# Sensor_Board.net
KiCad netlist of a schematic drawn in Altium Designer
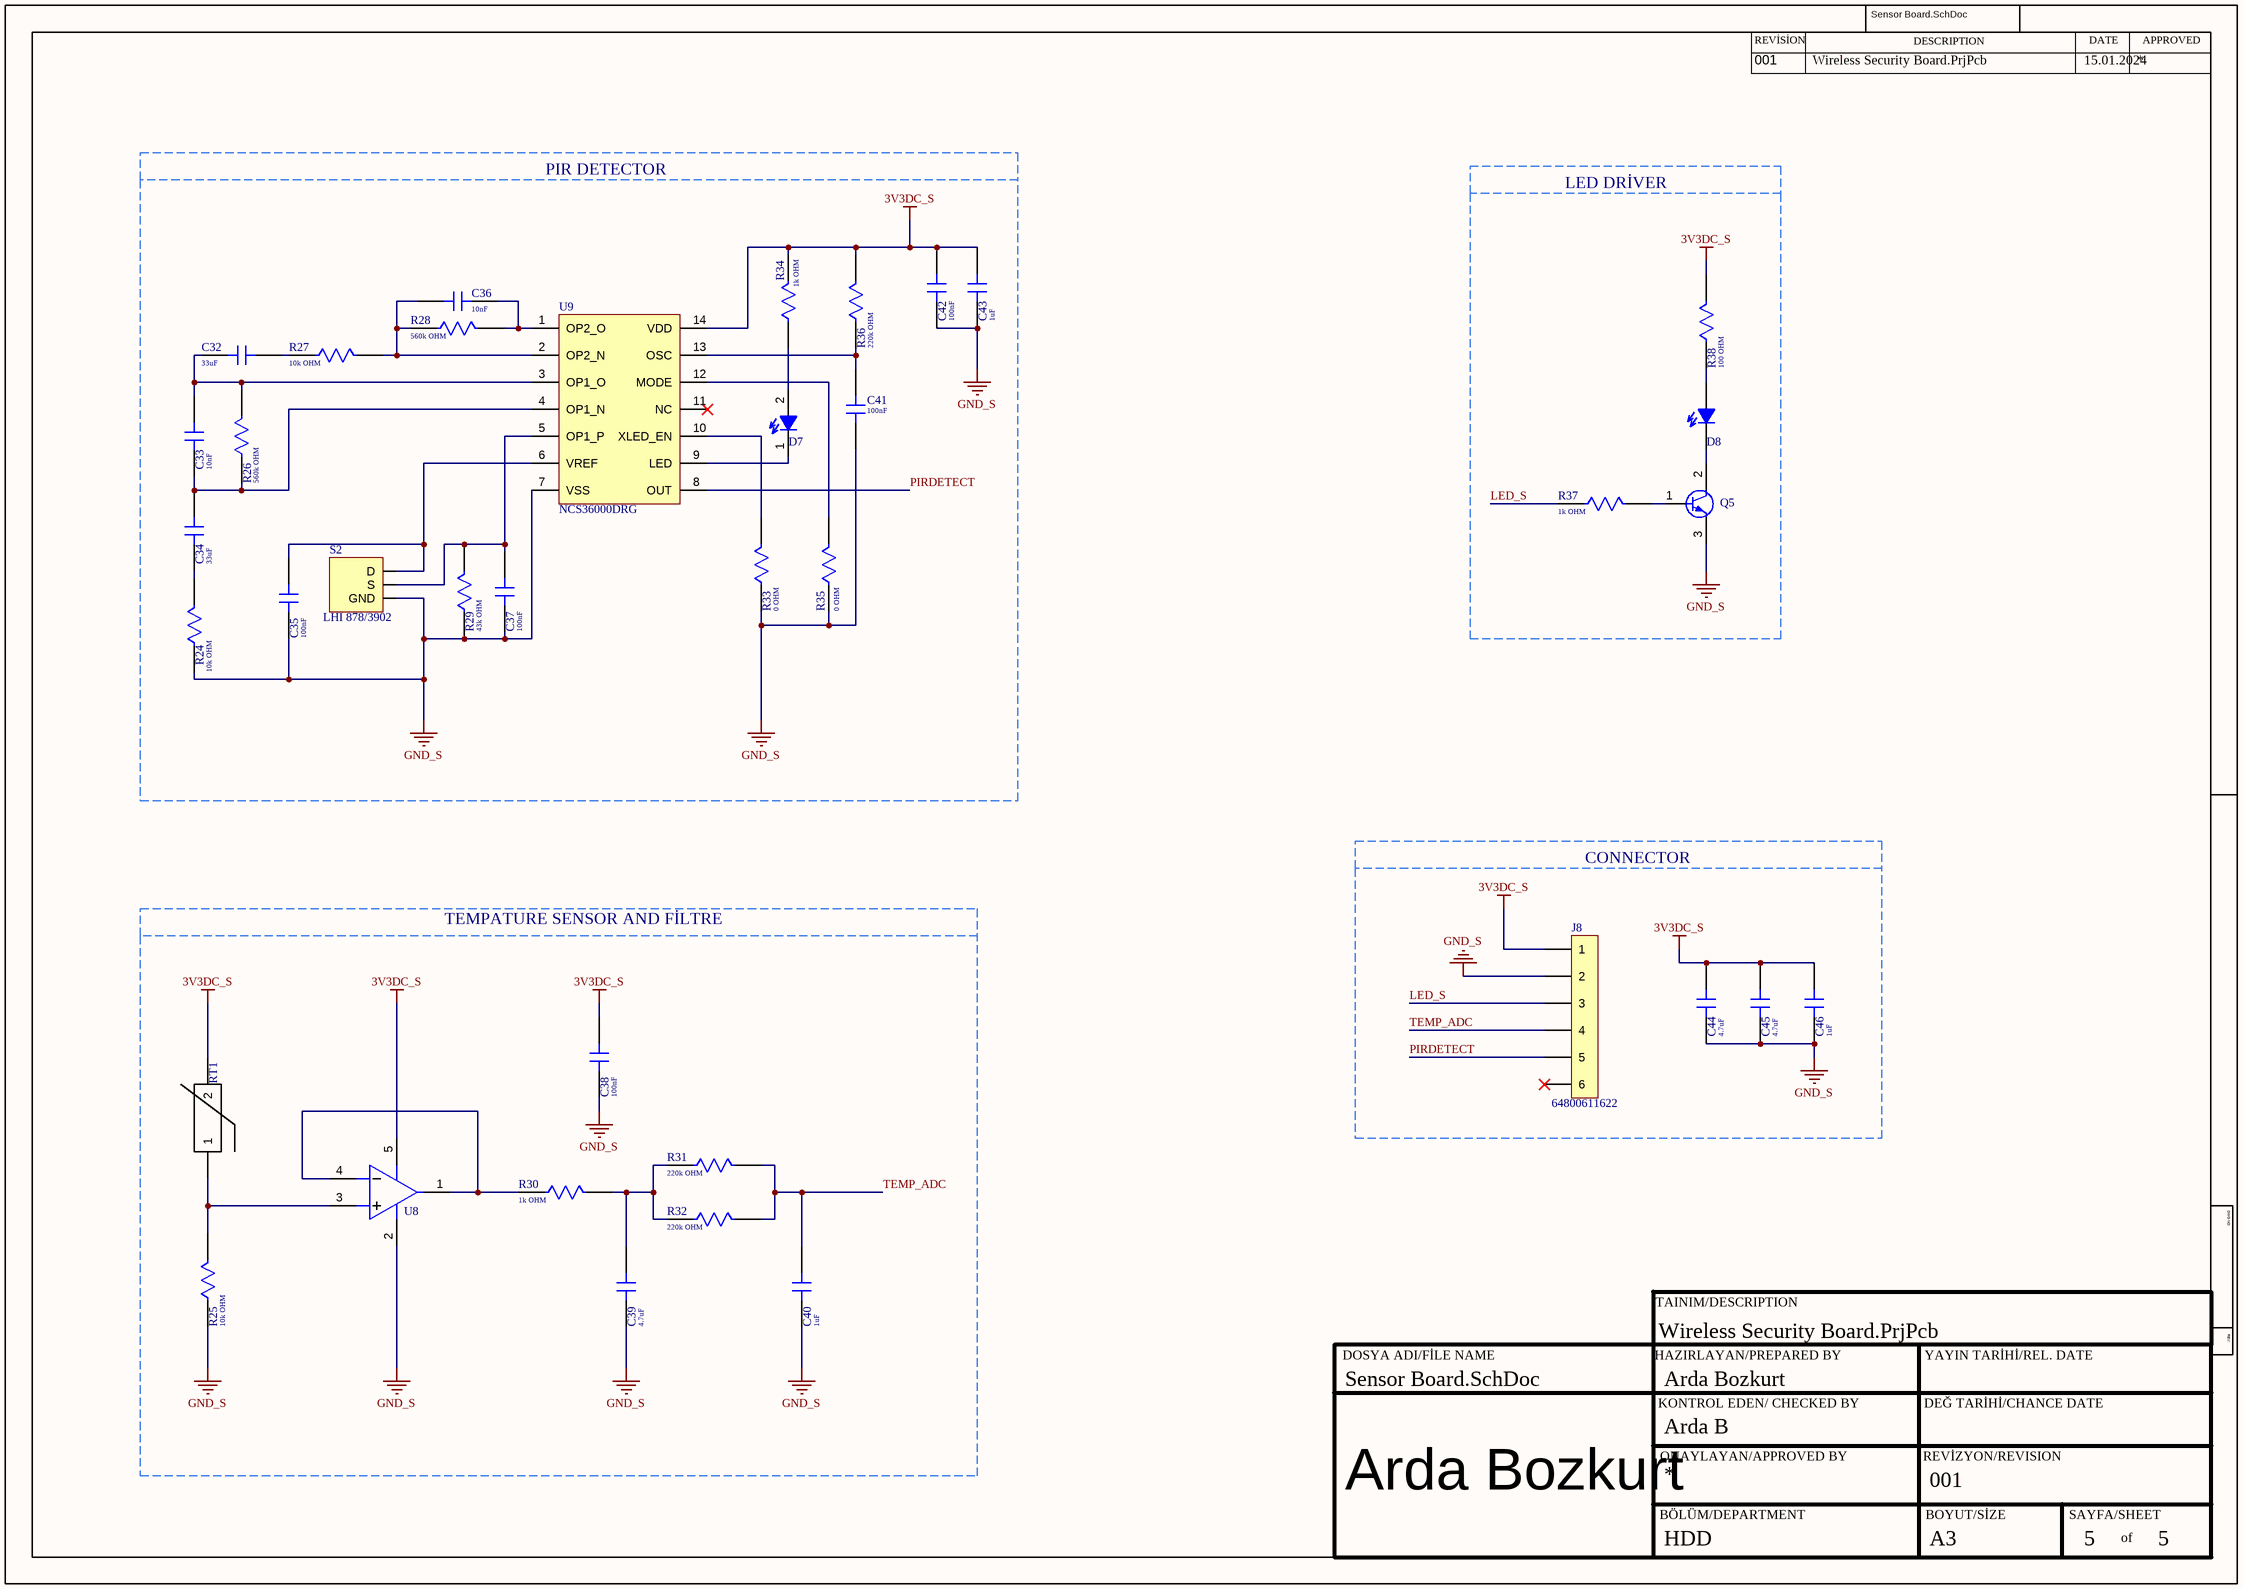
[diagram p0: Sensor Board.SchDoc]

(export (version "E")
  (design (tool "Eeschema 10.0.6"))
  (components
    (comp (ref "C32")
      (value "33uF")
      (footprint "CAP 1206")
      (description "C Series 1206 33 uF 16 V ±20 % Tolerance X5R SMT Multilayer Ceramic Capacitor")
      (fields
        (field (name "MANUFACTURER") "TDK")
        (field (name "MANUFACTURER PART NUMBER") "C3216X5R1C336M160AB")
        (field (name "DESIGNED BY.") "Arda B.")
      )
      (libsource (lib "FİRST.PROJECT.LİBRARY.~(1)") (part "CAP CER 33uF 1206"))
    )
    (comp (ref "C33")
      (value "10nF")
      (footprint "CAP-0603")
      (description "0603 16V X7R .01uF 10% multilayer ceramic capacitor")
      (fields
        (field (name "MANUFACTURER") "Walsin Technologies")
        (field (name "MANUFACTURER PART NUMBER") "0603B103K160CT")
        (field (name "DESIGNED BY") "Arda B.")
      )
      (libsource (lib "FİRST.PROJECT.LİBRARY.~(1)") (part "CAP CER 10nF 0603"))
    )
    (comp (ref "C34")
      (value "33uF")
      (footprint "CAP 1206")
      (description "C Series 1206 33 uF 16 V ±20 % Tolerance X5R SMT Multilayer Ceramic Capacitor")
      (fields
        (field (name "MANUFACTURER") "TDK")
        (field (name "MANUFACTURER PART NUMBER") "C3216X5R1C336M160AB")
        (field (name "DESIGNED BY.") "Arda B.")
      )
      (libsource (lib "FİRST.PROJECT.LİBRARY.~(1)") (part "CAP CER 33uF 1206"))
    )
    (comp (ref "C35")
      (value "100nF")
      (footprint "CAP-0805")
      (description "Multilayer Ceramic Capacitor, 0.1 uF, 50 V, ± 10%, X7R, 0805 [2012 Metric]")
      (fields
        (field (name "MANUFACTURER") "Kyocera AVX")
        (field (name "MANUFACTURER PART NUMBER") "08055C104KAT2A")
        (field (name "DESIGNED BY") "Arda B.")
      )
      (libsource (lib "FİRST.PROJECT.LİBRARY.~(1)") (part "CAP CER 100nF 0805"))
    )
    (comp (ref "C36")
      (value "10nF")
      (footprint "CAP-0603")
      (description "0603 16V X7R .01uF 10% multilayer ceramic capacitor")
      (fields
        (field (name "MANUFACTURER") "Walsin Technologies")
        (field (name "MANUFACTURER PART NUMBER") "0603B103K160CT")
        (field (name "DESIGNED BY") "Arda B.")
      )
      (libsource (lib "FİRST.PROJECT.LİBRARY.~(1)") (part "CAP CER 10nF 0603"))
    )
    (comp (ref "C37")
      (value "100nF")
      (footprint "CAP-0805")
      (description "Multilayer Ceramic Capacitor, 0.1 uF, 50 V, ± 10%, X7R, 0805 [2012 Metric]")
      (fields
        (field (name "MANUFACTURER") "Kyocera AVX")
        (field (name "MANUFACTURER PART NUMBER") "08055C104KAT2A")
        (field (name "DESIGNED BY") "Arda B.")
      )
      (libsource (lib "FİRST.PROJECT.LİBRARY.~(1)") (part "CAP CER 100nF 0805"))
    )
    (comp (ref "C38")
      (value "100nF")
      (footprint "CAP-0603")
      (description "Capacitor, 0.1UF, 100V, MLCC, 0603;")
      (fields
        (field (name "MANUFACTURER") "KEMET")
        (field (name "MANUFACTURER PART NUMBER") "C0603C104K1RACTU")
        (field (name "DESIGNED BY") "Arda B.")
      )
      (libsource (lib "FİRST.PROJECT.LİBRARY.~(1)") (part "CAP CER 100nF 0603"))
    )
    (comp (ref "C39")
      (value "4.7uF")
      (footprint "CAP-0805")
      (description "Multilayer Ceramic Capacitor, 4.7 uF, 25 V, ± 10%, X5R, 0805 [2012 Metric]")
      (fields
        (field (name "MANUFACTURER") "Samsung")
        (field (name "MANUFACTURER PART NUMBER") "CL21A475KAQNNNE")
        (field (name "DESIGNED BY") "Arda B.")
      )
      (libsource (lib "FİRST.PROJECT.LİBRARY.~(1)") (part "CAP CER 4.7uF 0805"))
    )
    (comp (ref "C40")
      (value "1uF")
      (footprint "CAP-0805")
      (description "Multilayer Ceramic Capacitor, 1 uF, 25 V, ± 10%, X7R, 0805 [2012 Metric]")
      (fields
        (field (name "MANUFACTURER") "Samsung")
        (field (name "MANUFACTURER PART NUMBER") "CL21B105KAFNNNE")
        (field (name "DESIGNED BY") "Arda B.")
      )
      (libsource (lib "FİRST.PROJECT.LİBRARY.~(1)") (part "CAP CER 1uF 0805"))
    )
    (comp (ref "C41")
      (value "100nF")
      (footprint "CAP-0805")
      (description "Multilayer Ceramic Capacitor, 0.1 uF, 50 V, ± 10%, X7R, 0805 [2012 Metric]")
      (fields
        (field (name "MANUFACTURER") "Kyocera AVX")
        (field (name "MANUFACTURER PART NUMBER") "08055C104KAT2A")
        (field (name "DESIGNED BY") "Arda B.")
      )
      (libsource (lib "FİRST.PROJECT.LİBRARY.~(1)") (part "CAP CER 100nF 0805"))
    )
    (comp (ref "C42")
      (value "100nF")
      (footprint "CAP-0805")
      (description "Multilayer Ceramic Capacitor, 0.1 uF, 50 V, ± 10%, X7R, 0805 [2012 Metric]")
      (fields
        (field (name "MANUFACTURER") "Kyocera AVX")
        (field (name "MANUFACTURER PART NUMBER") "08055C104KAT2A")
        (field (name "DESIGNED BY") "Arda B.")
      )
      (libsource (lib "FİRST.PROJECT.LİBRARY.~(1)") (part "CAP CER 100nF 0805"))
    )
    (comp (ref "C43")
      (value "1uF")
      (footprint "CAP-0805")
      (description "Multilayer Ceramic Capacitor, 1 uF, 25 V, ± 10%, X7R, 0805 [2012 Metric]")
      (fields
        (field (name "MANUFACTURER") "Samsung")
        (field (name "MANUFACTURER PART NUMBER") "CL21B105KAFNNNE")
        (field (name "DESIGNED BY") "Arda B.")
      )
      (libsource (lib "FİRST.PROJECT.LİBRARY.~(1)") (part "CAP CER 1uF 0805"))
    )
    (comp (ref "C44")
      (value "4.7uF")
      (footprint "CAP-0805")
      (description "Multilayer Ceramic Capacitor, 4.7 uF, 25 V, ± 10%, X5R, 0805 [2012 Metric]")
      (fields
        (field (name "MANUFACTURER") "Samsung")
        (field (name "MANUFACTURER PART NUMBER") "CL21A475KAQNNNE")
        (field (name "DESIGNED BY") "Arda B.")
      )
      (libsource (lib "FİRST.PROJECT.LİBRARY.~(1)") (part "CAP CER 4.7uF 0805"))
    )
    (comp (ref "C45")
      (value "4.7uF")
      (footprint "CAP-0805")
      (description "Multilayer Ceramic Capacitor, 4.7 uF, 25 V, ± 10%, X5R, 0805 [2012 Metric]")
      (fields
        (field (name "MANUFACTURER") "Samsung")
        (field (name "MANUFACTURER PART NUMBER") "CL21A475KAQNNNE")
        (field (name "DESIGNED BY") "Arda B.")
      )
      (libsource (lib "FİRST.PROJECT.LİBRARY.~(1)") (part "CAP CER 4.7uF 0805"))
    )
    (comp (ref "C46")
      (value "1uF")
      (footprint "CAP-0805")
      (description "Multilayer Ceramic Capacitor, 1 uF, 25 V, ± 10%, X7R, 0805 [2012 Metric]")
      (fields
        (field (name "MANUFACTURER") "Samsung")
        (field (name "MANUFACTURER PART NUMBER") "CL21B105KAFNNNE")
        (field (name "DESIGNED BY") "Arda B.")
      )
      (libsource (lib "FİRST.PROJECT.LİBRARY.~(1)") (part "CAP CER 1uF 0805"))
    )
    (comp (ref "D7")
      (value "LTST-C171GKT")
      (footprint "LED GREEN 0805")
      (description "LED Low-Power Uni-Color Green 565nm 2.1V 2-Pin Chip LED T/R")
      (fields (field (name "MANUFACTURER") "Vishay Lite-On") (field (name "DESIGNED BY") "Arda B."))
      (libsource (lib "FİRST.PROJECT.LİBRARY.~(1)") (part "LED GREEN 0805"))
    )
    (comp (ref "D8")
      (value "LS R976-NR-1")
      (footprint "LED RED 0805")
      (description "LED Uni-Color Super Red 645nm 2-Pin Chip 0805(2012Metric) T/R")
      (fields
        (field (name "MANUFACTURER") "Osram Opto")
        (field (name "MANUFACTURER PART NUMBER") "LSR976-NR-1")
        (field (name "DESIGNED BY") "Arda B.")
      )
      (libsource (lib "FİRST.PROJECT.LİBRARY.~(1)") (part "LED RED 0805"))
    )
    (comp (ref "J8")
      (value "64800611622")
      (footprint "PİN_HEADER_1X6")
      (description "WR-WTB Wire-to-Board Connectors 1.50 mm")
      (fields (field (name "MANUFACTURER") "Wurth Electronics") (field (name "DESIGNED BY.") "Arda B."))
      (libsource (lib "FİRST.PROJECT.LİBRARY.~(1)") (part "PİN HEADER 1X6"))
    )
    (comp (ref "Q5")
      (value "MMBT3904-7-F")
      (footprint "SOT23-3")
      (description "Transistor General Purpose BJT NPN 40 Volt 0.2A Automotive 3-Pin SOT-23")
      (fields (field (name "MANUFACTURER") "Diodes Zetex") (field (name "DESIGNED BY") "Arda B."))
      (libsource (lib "FİRST.PROJECT.LİBRARY.~(1)") (part "MMBT3904-7-F"))
    )
    (comp (ref "R24")
      (value "10k OHM")
      (footprint "RES-0603")
      (description "SMD Chip Resistor, 10 kOhm, ± 1%, 100 mW, 0603 [1608 Metric], Thick Film, General Purpose")
      (fields
        (field (name "MANUFACTURER") "Yageo")
        (field (name "MANUFACTURER PART NUMBER") "RC0603FR-0710KL")
        (field (name "DESIGNED BY") "Arda B.")
      )
      (libsource (lib "FİRST.PROJECT.LİBRARY.~(1)") (part "RES 10K OHM 0603"))
    )
    (comp (ref "R25")
      (value "10k OHM")
      (footprint "RES-0603")
      (description "SMD Chip Resistor, 10 kOhm, ± 1%, 100 mW, 0603 [1608 Metric], Thick Film, General Purpose")
      (fields
        (field (name "MANUFACTURER") "Yageo")
        (field (name "MANUFACTURER PART NUMBER") "RC0603FR-0710KL")
        (field (name "DESIGNED BY") "Arda B.")
      )
      (libsource (lib "FİRST.PROJECT.LİBRARY.~(1)") (part "RES 10K OHM 0603"))
    )
    (comp (ref "R26")
      (value "560k OHM")
      (footprint "RES-0603")
      (description "Res Thick Film 0603 560K Ohm 1% 1/10W ±100ppm/°C Molded SMD SMD Paper T/R")
      (fields
        (field (name "MANUFACTURER") "Stackpole Electronics")
        (field (name "MANUFACTURER PART NUMBER") "RMCF0603FT560K")
        (field (name "DESIGNED BY") "Arda B.")
      )
      (libsource (lib "FİRST.PROJECT.LİBRARY.~(1)") (part "RES 560K OHM 0603"))
    )
    (comp (ref "R27")
      (value "10k OHM")
      (footprint "RES-0603")
      (description "SMD Chip Resistor, 10 kOhm, ± 1%, 100 mW, 0603 [1608 Metric], Thick Film, General Purpose")
      (fields
        (field (name "MANUFACTURER") "Yageo")
        (field (name "MANUFACTURER PART NUMBER") "RC0603FR-0710KL")
        (field (name "DESIGNED BY") "Arda B.")
      )
      (libsource (lib "FİRST.PROJECT.LİBRARY.~(1)") (part "RES 10K OHM 0603"))
    )
    (comp (ref "R28")
      (value "560k OHM")
      (footprint "RES-0603")
      (description "Res Thick Film 0603 560K Ohm 1% 1/10W ±100ppm/°C Molded SMD SMD Paper T/R")
      (fields
        (field (name "MANUFACTURER") "Stackpole Electronics")
        (field (name "MANUFACTURER PART NUMBER") "RMCF0603FT560K")
        (field (name "DESIGNED BY") "Arda B.")
      )
      (libsource (lib "FİRST.PROJECT.LİBRARY.~(1)") (part "RES 560K OHM 0603"))
    )
    (comp (ref "R29")
      (value "43k OHM")
      (footprint "RES-0603")
      (description "Res Thick Film 0603 43K Ohm 1% 1/10W ±100ppm/°C Molded SMD SMD Paper T/R")
      (fields
        (field (name "MANUFACTURER") "Stackpole Electronics")
        (field (name "MANUFACTURER PART NUMBER") "RMCF0603FT43K0")
        (field (name "DESIGNED BY") "Arda B.")
      )
      (libsource (lib "FİRST.PROJECT.LİBRARY.~(1)") (part "RES 43K OHM 0603"))
    )
    (comp (ref "R30")
      (value "1k OHM")
      (footprint "RES-0603")
      (description "Res Thick Film 0603 1K Ohm 1% 0.1W(1/10W) ±100ppm/C Pad SMD Automotive T/R")
      (fields
        (field (name "MANUFACTURER") "Stackpole Electronics")
        (field (name "MANUFACTURER PART NUMBER") "RMCF0603FT1K00")
        (field (name "DESIGNED BY") "Arda B.")
      )
      (libsource (lib "FİRST.PROJECT.LİBRARY.~(1)") (part "RES 1K OHM 0603"))
    )
    (comp (ref "R31")
      (value "220k OHM")
      (footprint "RES-0603")
      (description "Res Thick Film 0603 220K Ohm 1% 0.1W(1/10W) ±100ppm/C Pad SMD T/R")
      (fields
        (field (name "MANUFACTURER") "Walsin Technologies")
        (field (name "MANUFACTURER PART NUMBER") "WR06X2203FTL")
        (field (name "DESIGNED BY") "Arda B.")
      )
      (libsource (lib "FİRST.PROJECT.LİBRARY.~(1)") (part "RES 220K OHM 0603"))
    )
    (comp (ref "R32")
      (value "220k OHM")
      (footprint "RES-0603")
      (description "Res Thick Film 0603 220K Ohm 1% 0.1W(1/10W) ±100ppm/C Pad SMD T/R")
      (fields
        (field (name "MANUFACTURER") "Walsin Technologies")
        (field (name "MANUFACTURER PART NUMBER") "WR06X2203FTL")
        (field (name "DESIGNED BY") "Arda B.")
      )
      (libsource (lib "FİRST.PROJECT.LİBRARY.~(1)") (part "RES 220K OHM 0603"))
    )
    (comp (ref "R33")
      (value "0 OHM")
      (footprint "RES-0603")
      (description "Res Thkflm 0603 0 Ohm Jumper 1/10W 100Ppm/ C Smd Rohs Compliant: Yes")
      (fields
        (field (name "MANUFACTURER") "Stackpole Electronics")
        (field (name "MANUFACTURER PART NUMBER") "RMCF0603ZT0R00")
        (field (name "DESIGNED BY") "Arda B.")
      )
      (libsource (lib "FİRST.PROJECT.LİBRARY.~(1)") (part "RES 0K OHM 0603"))
    )
    (comp (ref "R34")
      (value "1k OHM")
      (footprint "RES-0603")
      (description "Res Thick Film 0603 1K Ohm 1% 0.1W(1/10W) ±100ppm/C Pad SMD Automotive T/R")
      (fields
        (field (name "MANUFACTURER") "Stackpole Electronics")
        (field (name "MANUFACTURER PART NUMBER") "RMCF0603FT1K00")
        (field (name "DESIGNED BY") "Arda B.")
      )
      (libsource (lib "FİRST.PROJECT.LİBRARY.~(1)") (part "RES 1K OHM 0603"))
    )
    (comp (ref "R35")
      (value "0 OHM")
      (footprint "RES-0603")
      (description "Res Thkflm 0603 0 Ohm Jumper 1/10W 100Ppm/ C Smd Rohs Compliant: Yes")
      (fields
        (field (name "MANUFACTURER") "Stackpole Electronics")
        (field (name "MANUFACTURER PART NUMBER") "RMCF0603ZT0R00")
        (field (name "DESIGNED BY") "Arda B.")
      )
      (libsource (lib "FİRST.PROJECT.LİBRARY.~(1)") (part "RES 0K OHM 0603"))
    )
    (comp (ref "R36")
      (value "220k OHM")
      (footprint "RES-0603")
      (description "Res Thick Film 0603 220K Ohm 1% 0.1W(1/10W) ±100ppm/C Pad SMD T/R")
      (fields
        (field (name "MANUFACTURER") "Walsin Technologies")
        (field (name "MANUFACTURER PART NUMBER") "WR06X2203FTL")
        (field (name "DESIGNED BY") "Arda B.")
      )
      (libsource (lib "FİRST.PROJECT.LİBRARY.~(1)") (part "RES 220K OHM 0603"))
    )
    (comp (ref "R37")
      (value "1k OHM")
      (footprint "RES-0603")
      (description "Res Thick Film 0603 1K Ohm 1% 0.1W(1/10W) ±100ppm/C Pad SMD Automotive T/R")
      (fields
        (field (name "MANUFACTURER") "Stackpole Electronics")
        (field (name "MANUFACTURER PART NUMBER") "RMCF0603FT1K00")
        (field (name "DESIGNED BY") "Arda B.")
      )
      (libsource (lib "FİRST.PROJECT.LİBRARY.~(1)") (part "RES 1K OHM 0603"))
    )
    (comp (ref "R38")
      (value "100 OHM")
      (footprint "RES-0603")
      (description "Res Thick Film 0603 100 Ohm 1% 1/10W ±100ppm/°C Molded SMD SMD Paper T/R")
      (fields
        (field (name "MANUFACTURER") "Stackpole Electronics")
        (field (name "MANUFACTURER PART NUMBER") "RMCF0603FT100R")
        (field (name "DESIGNED BY") "Arda B.")
      )
      (libsource (lib "FİRST.PROJECT.LİBRARY.~(1)") (part "RES 100 OHM 0603"))
    )
    (comp (ref "RT1")
      (value "TFPT1206L1002FM")
      (footprint "TFPT1206")
      (description "Thermistor PTC 10K Ohm 1% 2-Pin 1206 Surface Mount Solder Pad T/R Automotive")
      (fields
        (field (name "MANUFACTURER") "Vishay Dale")
        (field (name "TOLERANCE") "1%")
        (field (name "DESIGNED BY") "Arda B.")
      )
      (libsource (lib "FİRST.PROJECT.LİBRARY.~(1)") (part "TFPT1206L1002FM"))
    )
    (comp (ref "S2")
      (value "LHI 878/3902")
      (footprint "TO-5-3")
      (description "SENSOR PYRO DETECTOR DUAL MOTION")
      (libsource (lib "FİRST.PROJECT.LİBRARY.~(1)") (part "LHI878/3902"))
    )
    (comp (ref "U8")
      (value "OPA314AIDBVR")
      (footprint "SOT23-5")
      (description "IC OPAMP GP 3MHZ RRO SOT23-5")
      (fields (field (name "MANUFACTURER") "Texas Instruments") (field (name "DESIGNED BY") "Arda B."))
      (libsource (lib "FİRST.PROJECT.LİBRARY.~(1)") (part "OPA 314"))
    )
    (comp (ref "U9")
      (value "NCS36000DRG")
      (footprint "SOIC-14")
      (description "PIR CONTROLLER NCS36000 Series Single 5.75V Passive Infrared Detector Controller (PIR) -SOIC-14")
      (fields (field (name "MANUFACTURER") "ON Semiconductor") (field (name "DESIGNED BY") "Arda B."))
      (libsource (lib "FİRST.PROJECT.LİBRARY.~(1)") (part "NCS36000"))
    )
  )
  (nets
    (net (code "1") (name "/LED_S") (class "Default")
      (node (ref "J8") (pin "3") (pinfunction "3_3") (pintype "power_in"))
      (node (ref "R37") (pin "1") (pinfunction "1_1") (pintype "passive"))
    )
    (net (code "2") (name "/PIRDETECT") (class "Default")
      (node (ref "J8") (pin "5") (pinfunction "5_5") (pintype "power_in"))
      (node (ref "U9") (pin "8") (pinfunction "OUT_8") (pintype "passive"))
    )
    (net (code "3") (name "/TEMP_ADC") (class "Default")
      (node (ref "C40") (pin "2") (pinfunction "2_2") (pintype "passive"))
      (node (ref "J8") (pin "4") (pinfunction "4_4") (pintype "power_in"))
      (node (ref "R31") (pin "2") (pinfunction "2_2") (pintype "passive"))
      (node (ref "R32") (pin "2") (pinfunction "2_2") (pintype "passive"))
    )
    (net (code "4") (name "3V3DC_S") (class "Default")
      (node (ref "C38") (pin "2") (pinfunction "2_2") (pintype "passive"))
      (node (ref "C42") (pin "2") (pinfunction "2_2") (pintype "passive"))
      (node (ref "C43") (pin "2") (pinfunction "2_2") (pintype "passive"))
      (node (ref "C44") (pin "2") (pinfunction "2_2") (pintype "passive"))
      (node (ref "C45") (pin "2") (pinfunction "2_2") (pintype "passive"))
      (node (ref "C46") (pin "2") (pinfunction "2_2") (pintype "passive"))
      (node (ref "J8") (pin "1") (pinfunction "1_1") (pintype "power_in"))
      (node (ref "R34") (pin "2") (pinfunction "2_2") (pintype "passive"))
      (node (ref "R36") (pin "2") (pinfunction "2_2") (pintype "passive"))
      (node (ref "R38") (pin "2") (pinfunction "2_2") (pintype "passive"))
      (node (ref "RT1") (pin "2") (pinfunction "2_2") (pintype "passive"))
      (node (ref "U8") (pin "5") (pinfunction "VCC+_5") (pintype "passive"))
      (node (ref "U9") (pin "14") (pinfunction "VDD_14") (pintype "passive"))
    )
    (net (code "5") (name "GND_S") (class "Default")
      (node (ref "C35") (pin "1") (pinfunction "1_1") (pintype "passive"))
      (node (ref "C37") (pin "1") (pinfunction "1_1") (pintype "passive"))
      (node (ref "C38") (pin "1") (pinfunction "1_1") (pintype "passive"))
      (node (ref "C39") (pin "1") (pinfunction "1_1") (pintype "passive"))
      (node (ref "C40") (pin "1") (pinfunction "1_1") (pintype "passive"))
      (node (ref "C41") (pin "1") (pinfunction "1_1") (pintype "passive"))
      (node (ref "C42") (pin "1") (pinfunction "1_1") (pintype "passive"))
      (node (ref "C43") (pin "1") (pinfunction "1_1") (pintype "passive"))
      (node (ref "C44") (pin "1") (pinfunction "1_1") (pintype "passive"))
      (node (ref "C45") (pin "1") (pinfunction "1_1") (pintype "passive"))
      (node (ref "C46") (pin "1") (pinfunction "1_1") (pintype "passive"))
      (node (ref "J8") (pin "2") (pinfunction "2_2") (pintype "power_in"))
      (node (ref "Q5") (pin "3") (pinfunction "E_3") (pintype "passive"))
      (node (ref "R24") (pin "1") (pinfunction "1_1") (pintype "passive"))
      (node (ref "R25") (pin "1") (pinfunction "1_1") (pintype "passive"))
      (node (ref "R29") (pin "1") (pinfunction "1_1") (pintype "passive"))
      (node (ref "R33") (pin "1") (pinfunction "1_1") (pintype "passive"))
      (node (ref "R35") (pin "1") (pinfunction "1_1") (pintype "passive"))
      (node (ref "S2") (pin "3") (pinfunction "GND_3") (pintype "passive"))
      (node (ref "U8") (pin "2") (pinfunction "VCC-_2") (pintype "passive"))
      (node (ref "U9") (pin "7") (pinfunction "VSS_7") (pintype "passive"))
    )
    (net (code "6") (name "Net-(C32-Pad2)") (class "Default")
      (node (ref "C32") (pin "2") (pinfunction "2_2") (pintype "passive"))
      (node (ref "R27") (pin "1") (pinfunction "1_1") (pintype "passive"))
    )
    (net (code "7") (name "Net-(C34-Pad1)") (class "Default")
      (node (ref "C34") (pin "1") (pinfunction "1_1") (pintype "passive"))
      (node (ref "R24") (pin "2") (pinfunction "2_2") (pintype "passive"))
    )
    (net (code "8") (name "Net-(C39-Pad2)") (class "Default")
      (node (ref "C39") (pin "2") (pinfunction "2_2") (pintype "passive"))
      (node (ref "R30") (pin "2") (pinfunction "2_2") (pintype "passive"))
      (node (ref "R31") (pin "1") (pinfunction "1_1") (pintype "passive"))
      (node (ref "R32") (pin "1") (pinfunction "1_1") (pintype "passive"))
    )
    (net (code "9") (name "Net-(D7-Pad2)") (class "Default")
      (node (ref "D7") (pin "2") (pinfunction "2_2") (pintype "passive"))
      (node (ref "R34") (pin "1") (pinfunction "1_1") (pintype "passive"))
    )
    (net (code "10") (name "Net-(D8-Pad2)") (class "Default")
      (node (ref "D8") (pin "2") (pinfunction "2_2") (pintype "passive"))
      (node (ref "R38") (pin "1") (pinfunction "1_1") (pintype "passive"))
    )
    (net (code "11") (name "Net-(Q5-B)") (class "Default")
      (node (ref "Q5") (pin "1") (pinfunction "B_1") (pintype "passive"))
      (node (ref "R37") (pin "2") (pinfunction "2_2") (pintype "passive"))
    )
    (net (code "12") (name "Net-(Q5-C)") (class "Default")
      (node (ref "D8") (pin "1") (pinfunction "1_1") (pintype "passive"))
      (node (ref "Q5") (pin "2") (pinfunction "C_2") (pintype "passive"))
    )
    (net (code "13") (name "Net-(S2-D)") (class "Default")
      (node (ref "C35") (pin "2") (pinfunction "2_2") (pintype "passive"))
      (node (ref "S2") (pin "1") (pinfunction "D_1") (pintype "passive"))
      (node (ref "U9") (pin "6") (pinfunction "VREF_6") (pintype "passive"))
    )
    (net (code "14") (name "Net-(S2-S)") (class "Default")
      (node (ref "C37") (pin "2") (pinfunction "2_2") (pintype "passive"))
      (node (ref "R29") (pin "2") (pinfunction "2_2") (pintype "passive"))
      (node (ref "S2") (pin "2") (pinfunction "S_2") (pintype "passive"))
      (node (ref "U9") (pin "5") (pinfunction "OP1_P_5") (pintype "passive"))
    )
    (net (code "15") (name "Net-(U8-IN+)") (class "Default")
      (node (ref "R25") (pin "2") (pinfunction "2_2") (pintype "passive"))
      (node (ref "RT1") (pin "1") (pinfunction "1_1") (pintype "passive"))
      (node (ref "U8") (pin "3") (pinfunction "IN+_3") (pintype "passive"))
    )
    (net (code "16") (name "Net-(U8-IN-)") (class "Default")
      (node (ref "R30") (pin "1") (pinfunction "1_1") (pintype "passive"))
      (node (ref "U8") (pin "1") (pinfunction "OUT_1") (pintype "passive"))
      (node (ref "U8") (pin "4") (pinfunction "IN-_4") (pintype "passive"))
    )
    (net (code "17") (name "Net-(U9-LED)") (class "Default")
      (node (ref "D7") (pin "1") (pinfunction "1_1") (pintype "passive"))
      (node (ref "U9") (pin "9") (pinfunction "LED_9") (pintype "passive"))
    )
    (net (code "18") (name "Net-(U9-MODE)") (class "Default")
      (node (ref "R35") (pin "2") (pinfunction "2_2") (pintype "passive"))
      (node (ref "U9") (pin "12") (pinfunction "MODE_12") (pintype "passive"))
    )
    (net (code "19") (name "Net-(U9-OP1_N)") (class "Default")
      (node (ref "C33") (pin "1") (pinfunction "1_1") (pintype "passive"))
      (node (ref "C34") (pin "2") (pinfunction "2_2") (pintype "passive"))
      (node (ref "R26") (pin "1") (pinfunction "1_1") (pintype "passive"))
      (node (ref "U9") (pin "4") (pinfunction "OP1_N_4") (pintype "passive"))
    )
    (net (code "20") (name "Net-(U9-OP1_O)") (class "Default")
      (node (ref "C32") (pin "1") (pinfunction "1_1") (pintype "passive"))
      (node (ref "C33") (pin "2") (pinfunction "2_2") (pintype "passive"))
      (node (ref "R26") (pin "2") (pinfunction "2_2") (pintype "passive"))
      (node (ref "U9") (pin "3") (pinfunction "OP1_O_3") (pintype "passive"))
    )
    (net (code "21") (name "Net-(U9-OP2_N)") (class "Default")
      (node (ref "C36") (pin "1") (pinfunction "1_1") (pintype "passive"))
      (node (ref "R27") (pin "2") (pinfunction "2_2") (pintype "passive"))
      (node (ref "R28") (pin "1") (pinfunction "1_1") (pintype "passive"))
      (node (ref "U9") (pin "2") (pinfunction "OP2_N_2") (pintype "passive"))
    )
    (net (code "22") (name "Net-(U9-OP2_O)") (class "Default")
      (node (ref "C36") (pin "2") (pinfunction "2_2") (pintype "passive"))
      (node (ref "R28") (pin "2") (pinfunction "2_2") (pintype "passive"))
      (node (ref "U9") (pin "1") (pinfunction "OP2_O_1") (pintype "passive"))
    )
    (net (code "23") (name "Net-(U9-OSC)") (class "Default")
      (node (ref "C41") (pin "2") (pinfunction "2_2") (pintype "passive"))
      (node (ref "R36") (pin "1") (pinfunction "1_1") (pintype "passive"))
      (node (ref "U9") (pin "13") (pinfunction "OSC_13") (pintype "passive"))
    )
    (net (code "24") (name "Net-(U9-XLED_EN)") (class "Default")
      (node (ref "R33") (pin "2") (pinfunction "2_2") (pintype "passive"))
      (node (ref "U9") (pin "10") (pinfunction "XLED_EN_10") (pintype "passive"))
    )
    (net (code "25") (name "unconnected-(J8-Pad6)") (class "Default")
      (node (ref "J8") (pin "6") (pinfunction "6_6") (pintype "power_in+no_connect"))
    )
    (net (code "26") (name "unconnected-(U9-NC-Pad11)") (class "Default")
      (node (ref "U9") (pin "11") (pinfunction "NC_11") (pintype "passive+no_connect"))
    )
  )
)
